# Core.net
KiCad netlist of a schematic drawn in Altium Designer
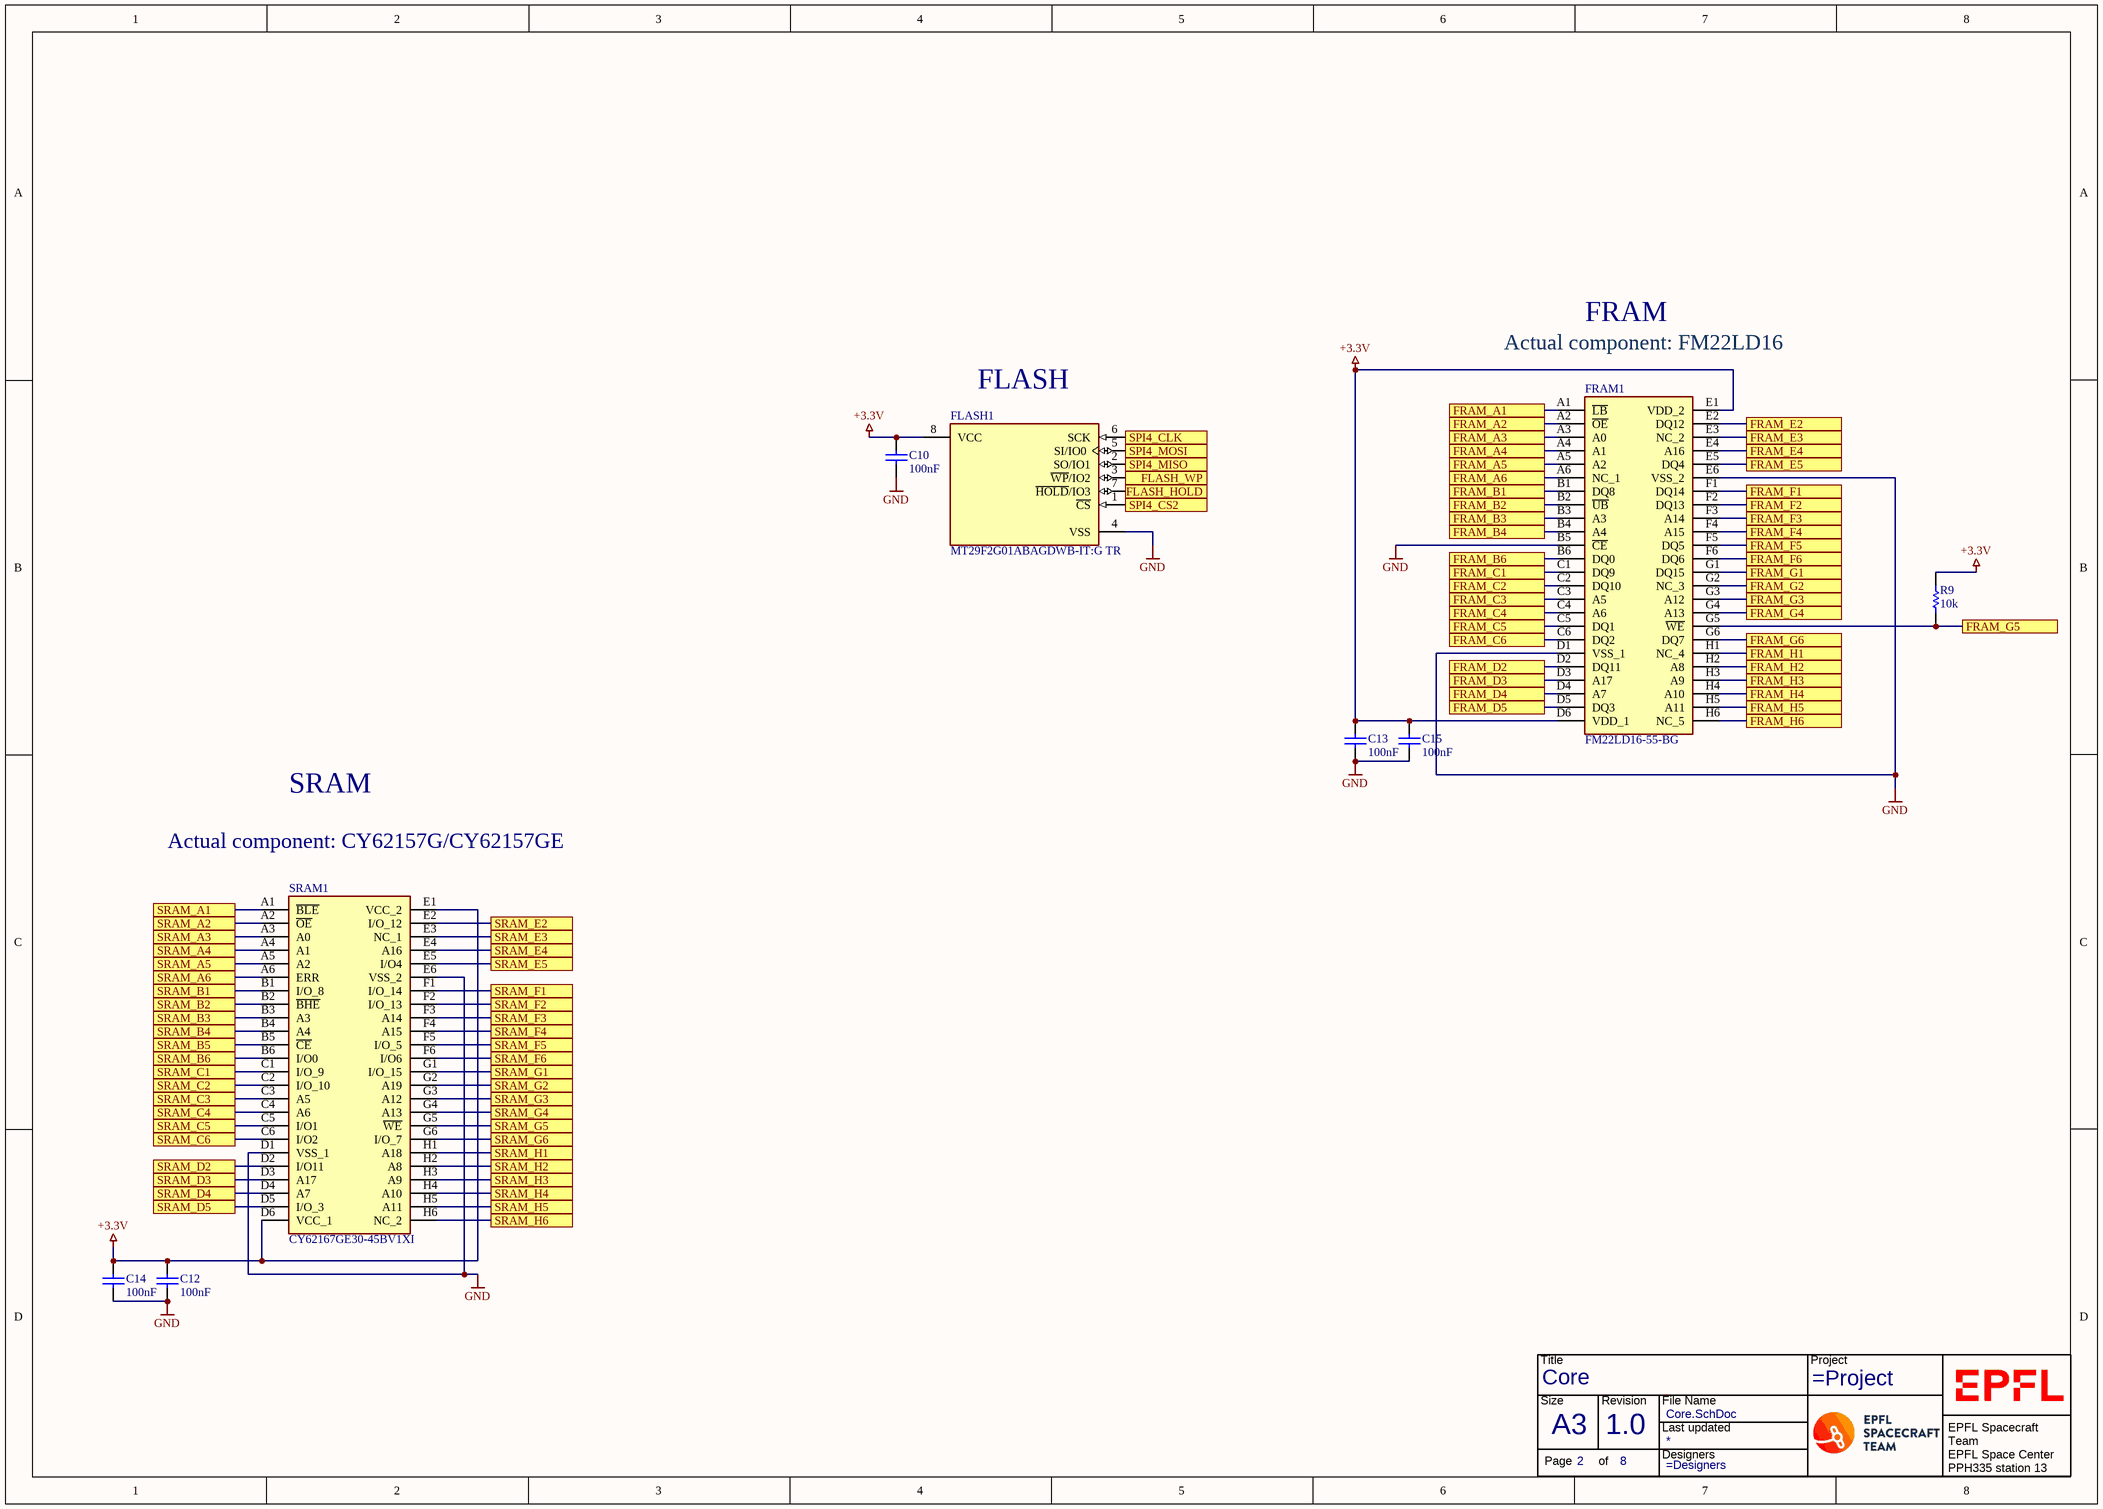
[diagram p0: Core.SchDoc]

(export (version "E")
  (design (tool "Eeschema 10.0.6"))
  (components
    (comp (ref "*")
      (value "TitleBlock")
      (description "Title Block with generall information")
      (libsource (lib "CHESSOBC_rev1") (part "TitleBlock"))
    )
    (comp (ref "C10")
      (value "100nF")
      (footprint "CAPC1005X60X30ML05T10")
      (fields (field (name "MANUFACTURER") "Kemet") (field (name "PART NUMBER") "C0402C104K8PACTU"))
      (libsource (lib "Altium Content Vault") (part "CAP"))
    )
    (comp (ref "C12")
      (value "100nF")
      (footprint "CAPC1005X60X30ML05T10")
      (fields (field (name "MANUFACTURER") "Kemet") (field (name "PART NUMBER") "C0402C104K8PACTU"))
      (libsource (lib "Altium Content Vault") (part "CAP"))
    )
    (comp (ref "C13")
      (value "100nF")
      (footprint "CAPC1005X60X30ML05T10")
      (fields (field (name "MANUFACTURER") "Kemet") (field (name "PART NUMBER") "C0402C104K8PACTU"))
      (libsource (lib "Altium Content Vault") (part "CAP"))
    )
    (comp (ref "C14")
      (value "100nF")
      (footprint "CAPC1005X60X30ML05T10")
      (fields (field (name "MANUFACTURER") "Kemet") (field (name "PART NUMBER") "C0402C104K8PACTU"))
      (libsource (lib "Altium Content Vault") (part "CAP"))
    )
    (comp (ref "C15")
      (value "100nF")
      (footprint "CAPC1005X60X30ML05T10")
      (fields (field (name "MANUFACTURER") "Kemet") (field (name "PART NUMBER") "C0402C104K8PACTU"))
      (libsource (lib "Altium Content Vault") (part "CAP"))
    )
    (comp (ref "FLASH1")
      (value "MT29F2G01ABAGDWB-IT:G TR")
      (footprint "FP-WB-IPC_C")
      (description "IC FLASH 2G SPI 8UPDFN")
      (libsource (lib "Altium Content Vault") (part "9be75b636f0445a1fe91e7781565aa2"))
    )
    (comp (ref "FRAM1")
      (value "FM22LD16-55-BG")
      (footprint "SamacSys:BGA48C75P6X8_600X800X120")
      (description "Integrated Circuit")
      (fields (field (name "MOUSER PART NUMBER") "877-FM22LD16-55-BG"))
      (libsource (lib "*") (part "FM22LD16-55-BG"))
    )
    (comp (ref "R9")
      (value "10k")
      (footprint "RESC1005X40X25LL05T10")
      (fields (field (name "PART NUMBER") "RC0402FR-0710KL") (field (name "MANUFACTURER") "Yageo / Phycomp"))
      (libsource (lib "Altium Content Vault") (part "RES"))
    )
    (comp (ref "SRAM1")
      (value "CY62167GE30-45BV1XI")
      (footprint "SamacSys:BGA48C75P6X8_600X800X100")
      (description "Integrated Circuit")
      (fields (field (name "MOUSER PART NUMBER") "727-CY62167GE30BV1XI"))
      (libsource (lib "*") (part "CY62167GE30-45BV1XI"))
    )
  )
  (nets
    (net (code "1") (name "+3.3V") (class "Default")
      (node (ref "C10") (pin "2") (pinfunction "2_2") (pintype "passive"))
      (node (ref "C12") (pin "2") (pinfunction "2_2") (pintype "passive"))
      (node (ref "C13") (pin "2") (pinfunction "2_2") (pintype "passive"))
      (node (ref "C14") (pin "2") (pinfunction "2_2") (pintype "passive"))
      (node (ref "C15") (pin "2") (pinfunction "2_2") (pintype "passive"))
      (node (ref "FLASH1") (pin "8") (pinfunction "VCC_8") (pintype "power_in"))
      (node (ref "FRAM1") (pin "D6") (pinfunction "VDD_1_D6") (pintype "passive"))
      (node (ref "FRAM1") (pin "E1") (pinfunction "VDD_2_E1") (pintype "passive"))
      (node (ref "R9") (pin "2") (pinfunction "2_2") (pintype "passive"))
      (node (ref "SRAM1") (pin "D6") (pinfunction "VCC_1_D6") (pintype "passive"))
      (node (ref "SRAM1") (pin "E1") (pinfunction "VCC_2_E1") (pintype "passive"))
    )
    (net (code "2") (name "/FLASH_HOLD") (class "Default")
      (node (ref "FLASH1") (pin "7") (pinfunction "~{HOLD}/IO3_7") (pintype "bidirectional"))
    )
    (net (code "3") (name "/FLASH_WP") (class "Default")
      (node (ref "FLASH1") (pin "3") (pinfunction "~{WP}/IO2_3") (pintype "bidirectional"))
    )
    (net (code "4") (name "/FRAM_A1") (class "Default")
      (node (ref "FRAM1") (pin "A1") (pinfunction "~{LB}_A1") (pintype "passive"))
    )
    (net (code "5") (name "/FRAM_A2") (class "Default")
      (node (ref "FRAM1") (pin "A2") (pinfunction "~{OE}_A2") (pintype "passive"))
    )
    (net (code "6") (name "/FRAM_A3") (class "Default")
      (node (ref "FRAM1") (pin "A3") (pinfunction "A0_A3") (pintype "passive"))
    )
    (net (code "7") (name "/FRAM_A4") (class "Default")
      (node (ref "FRAM1") (pin "A4") (pinfunction "A1_A4") (pintype "passive"))
    )
    (net (code "8") (name "/FRAM_A5") (class "Default")
      (node (ref "FRAM1") (pin "A5") (pinfunction "A2_A5") (pintype "passive"))
    )
    (net (code "9") (name "/FRAM_A6") (class "Default")
      (node (ref "FRAM1") (pin "A6") (pinfunction "NC_1_A6") (pintype "passive"))
    )
    (net (code "10") (name "/FRAM_B1") (class "Default")
      (node (ref "FRAM1") (pin "B1") (pinfunction "DQ8_B1") (pintype "passive"))
    )
    (net (code "11") (name "/FRAM_B2") (class "Default")
      (node (ref "FRAM1") (pin "B2") (pinfunction "~{UB}_B2") (pintype "passive"))
    )
    (net (code "12") (name "/FRAM_B3") (class "Default")
      (node (ref "FRAM1") (pin "B3") (pinfunction "A3_B3") (pintype "passive"))
    )
    (net (code "13") (name "/FRAM_B4") (class "Default")
      (node (ref "FRAM1") (pin "B4") (pinfunction "A4_B4") (pintype "passive"))
    )
    (net (code "14") (name "/FRAM_B6") (class "Default")
      (node (ref "FRAM1") (pin "B6") (pinfunction "DQ0_B6") (pintype "passive"))
    )
    (net (code "15") (name "/FRAM_C1") (class "Default")
      (node (ref "FRAM1") (pin "C1") (pinfunction "DQ9_C1") (pintype "passive"))
    )
    (net (code "16") (name "/FRAM_C2") (class "Default")
      (node (ref "FRAM1") (pin "C2") (pinfunction "DQ10_C2") (pintype "passive"))
    )
    (net (code "17") (name "/FRAM_C3") (class "Default")
      (node (ref "FRAM1") (pin "C3") (pinfunction "A5_C3") (pintype "passive"))
    )
    (net (code "18") (name "/FRAM_C4") (class "Default")
      (node (ref "FRAM1") (pin "C4") (pinfunction "A6_C4") (pintype "passive"))
    )
    (net (code "19") (name "/FRAM_C5") (class "Default")
      (node (ref "FRAM1") (pin "C5") (pinfunction "DQ1_C5") (pintype "passive"))
    )
    (net (code "20") (name "/FRAM_C6") (class "Default")
      (node (ref "FRAM1") (pin "C6") (pinfunction "DQ2_C6") (pintype "passive"))
    )
    (net (code "21") (name "/FRAM_D2") (class "Default")
      (node (ref "FRAM1") (pin "D2") (pinfunction "DQ11_D2") (pintype "passive"))
    )
    (net (code "22") (name "/FRAM_D3") (class "Default")
      (node (ref "FRAM1") (pin "D3") (pinfunction "A17_D3") (pintype "passive"))
    )
    (net (code "23") (name "/FRAM_D4") (class "Default")
      (node (ref "FRAM1") (pin "D4") (pinfunction "A7_D4") (pintype "passive"))
    )
    (net (code "24") (name "/FRAM_D5") (class "Default")
      (node (ref "FRAM1") (pin "D5") (pinfunction "DQ3_D5") (pintype "passive"))
    )
    (net (code "25") (name "/FRAM_E2") (class "Default")
      (node (ref "FRAM1") (pin "E2") (pinfunction "DQ12_E2") (pintype "passive"))
    )
    (net (code "26") (name "/FRAM_E3") (class "Default")
      (node (ref "FRAM1") (pin "E3") (pinfunction "NC_2_E3") (pintype "passive"))
    )
    (net (code "27") (name "/FRAM_E4") (class "Default")
      (node (ref "FRAM1") (pin "E4") (pinfunction "A16_E4") (pintype "passive"))
    )
    (net (code "28") (name "/FRAM_E5") (class "Default")
      (node (ref "FRAM1") (pin "E5") (pinfunction "DQ4_E5") (pintype "passive"))
    )
    (net (code "29") (name "/FRAM_F1") (class "Default")
      (node (ref "FRAM1") (pin "F1") (pinfunction "DQ14_F1") (pintype "passive"))
    )
    (net (code "30") (name "/FRAM_F2") (class "Default")
      (node (ref "FRAM1") (pin "F2") (pinfunction "DQ13_F2") (pintype "passive"))
    )
    (net (code "31") (name "/FRAM_F3") (class "Default")
      (node (ref "FRAM1") (pin "F3") (pinfunction "A14_F3") (pintype "passive"))
    )
    (net (code "32") (name "/FRAM_F4") (class "Default")
      (node (ref "FRAM1") (pin "F4") (pinfunction "A15_F4") (pintype "passive"))
    )
    (net (code "33") (name "/FRAM_F5") (class "Default")
      (node (ref "FRAM1") (pin "F5") (pinfunction "DQ5_F5") (pintype "passive"))
    )
    (net (code "34") (name "/FRAM_F6") (class "Default")
      (node (ref "FRAM1") (pin "F6") (pinfunction "DQ6_F6") (pintype "passive"))
    )
    (net (code "35") (name "/FRAM_G1") (class "Default")
      (node (ref "FRAM1") (pin "G1") (pinfunction "DQ15_G1") (pintype "passive"))
    )
    (net (code "36") (name "/FRAM_G2") (class "Default")
      (node (ref "FRAM1") (pin "G2") (pinfunction "NC_3_G2") (pintype "passive"))
    )
    (net (code "37") (name "/FRAM_G3") (class "Default")
      (node (ref "FRAM1") (pin "G3") (pinfunction "A12_G3") (pintype "passive"))
    )
    (net (code "38") (name "/FRAM_G4") (class "Default")
      (node (ref "FRAM1") (pin "G4") (pinfunction "A13_G4") (pintype "passive"))
    )
    (net (code "39") (name "/FRAM_G5") (class "Default")
      (node (ref "FRAM1") (pin "G5") (pinfunction "~{WE}_G5") (pintype "passive"))
      (node (ref "R9") (pin "1") (pinfunction "1_1") (pintype "passive"))
    )
    (net (code "40") (name "/FRAM_G6") (class "Default")
      (node (ref "FRAM1") (pin "G6") (pinfunction "DQ7_G6") (pintype "passive"))
    )
    (net (code "41") (name "/FRAM_H1") (class "Default")
      (node (ref "FRAM1") (pin "H1") (pinfunction "NC_4_H1") (pintype "passive"))
    )
    (net (code "42") (name "/FRAM_H2") (class "Default")
      (node (ref "FRAM1") (pin "H2") (pinfunction "A8_H2") (pintype "passive"))
    )
    (net (code "43") (name "/FRAM_H3") (class "Default")
      (node (ref "FRAM1") (pin "H3") (pinfunction "A9_H3") (pintype "passive"))
    )
    (net (code "44") (name "/FRAM_H4") (class "Default")
      (node (ref "FRAM1") (pin "H4") (pinfunction "A10_H4") (pintype "passive"))
    )
    (net (code "45") (name "/FRAM_H5") (class "Default")
      (node (ref "FRAM1") (pin "H5") (pinfunction "A11_H5") (pintype "passive"))
    )
    (net (code "46") (name "/FRAM_H6") (class "Default")
      (node (ref "FRAM1") (pin "H6") (pinfunction "NC_5_H6") (pintype "passive"))
    )
    (net (code "47") (name "/SPI4_CLK") (class "Default")
      (node (ref "FLASH1") (pin "6") (pinfunction "SCK_6") (pintype "input"))
    )
    (net (code "48") (name "/SPI4_CS2") (class "Default")
      (node (ref "FLASH1") (pin "1") (pinfunction "~{CS}_1") (pintype "input"))
    )
    (net (code "49") (name "/SPI4_MISO") (class "Default")
      (node (ref "FLASH1") (pin "2") (pinfunction "SO/IO1_2") (pintype "bidirectional"))
    )
    (net (code "50") (name "/SPI4_MOSI") (class "Default")
      (node (ref "FLASH1") (pin "5") (pinfunction "SI/IO0_5") (pintype "bidirectional"))
    )
    (net (code "51") (name "/SRAM_A1") (class "Default")
      (node (ref "SRAM1") (pin "A1") (pinfunction "~{BLE}_A1") (pintype "passive"))
    )
    (net (code "52") (name "/SRAM_A2") (class "Default")
      (node (ref "SRAM1") (pin "A2") (pinfunction "~{OE}_A2") (pintype "passive"))
    )
    (net (code "53") (name "/SRAM_A3") (class "Default")
      (node (ref "SRAM1") (pin "A3") (pinfunction "A0_A3") (pintype "passive"))
    )
    (net (code "54") (name "/SRAM_A4") (class "Default")
      (node (ref "SRAM1") (pin "A4") (pinfunction "A1_A4") (pintype "passive"))
    )
    (net (code "55") (name "/SRAM_A5") (class "Default")
      (node (ref "SRAM1") (pin "A5") (pinfunction "A2_A5") (pintype "passive"))
    )
    (net (code "56") (name "/SRAM_A6") (class "Default")
      (node (ref "SRAM1") (pin "A6") (pinfunction "ERR_A6") (pintype "passive"))
    )
    (net (code "57") (name "/SRAM_B1") (class "Default")
      (node (ref "SRAM1") (pin "B1") (pinfunction "I/O_8_B1") (pintype "passive"))
    )
    (net (code "58") (name "/SRAM_B2") (class "Default")
      (node (ref "SRAM1") (pin "B2") (pinfunction "~{BHE}_B2") (pintype "passive"))
    )
    (net (code "59") (name "/SRAM_B3") (class "Default")
      (node (ref "SRAM1") (pin "B3") (pinfunction "A3_B3") (pintype "passive"))
    )
    (net (code "60") (name "/SRAM_B4") (class "Default")
      (node (ref "SRAM1") (pin "B4") (pinfunction "A4_B4") (pintype "passive"))
    )
    (net (code "61") (name "/SRAM_B5") (class "Default")
      (node (ref "SRAM1") (pin "B5") (pinfunction "~{CE}_B5") (pintype "passive"))
    )
    (net (code "62") (name "/SRAM_B6") (class "Default")
      (node (ref "SRAM1") (pin "B6") (pinfunction "I/O0_B6") (pintype "passive"))
    )
    (net (code "63") (name "/SRAM_C1") (class "Default")
      (node (ref "SRAM1") (pin "C1") (pinfunction "I/O_9_C1") (pintype "passive"))
    )
    (net (code "64") (name "/SRAM_C2") (class "Default")
      (node (ref "SRAM1") (pin "C2") (pinfunction "I/O_10_C2") (pintype "passive"))
    )
    (net (code "65") (name "/SRAM_C3") (class "Default")
      (node (ref "SRAM1") (pin "C3") (pinfunction "A5_C3") (pintype "passive"))
    )
    (net (code "66") (name "/SRAM_C4") (class "Default")
      (node (ref "SRAM1") (pin "C4") (pinfunction "A6_C4") (pintype "passive"))
    )
    (net (code "67") (name "/SRAM_C5") (class "Default")
      (node (ref "SRAM1") (pin "C5") (pinfunction "I/O1_C5") (pintype "passive"))
    )
    (net (code "68") (name "/SRAM_C6") (class "Default")
      (node (ref "SRAM1") (pin "C6") (pinfunction "I/O2_C6") (pintype "passive"))
    )
    (net (code "69") (name "/SRAM_D2") (class "Default")
      (node (ref "SRAM1") (pin "D2") (pinfunction "I/O11_D2") (pintype "passive"))
    )
    (net (code "70") (name "/SRAM_D3") (class "Default")
      (node (ref "SRAM1") (pin "D3") (pinfunction "A17_D3") (pintype "passive"))
    )
    (net (code "71") (name "/SRAM_D4") (class "Default")
      (node (ref "SRAM1") (pin "D4") (pinfunction "A7_D4") (pintype "passive"))
    )
    (net (code "72") (name "/SRAM_D5") (class "Default")
      (node (ref "SRAM1") (pin "D5") (pinfunction "I/O_3_D5") (pintype "passive"))
    )
    (net (code "73") (name "/SRAM_E2") (class "Default")
      (node (ref "SRAM1") (pin "E2") (pinfunction "I/O_12_E2") (pintype "passive"))
    )
    (net (code "74") (name "/SRAM_E3") (class "Default")
      (node (ref "SRAM1") (pin "E3") (pinfunction "NC_1_E3") (pintype "passive"))
    )
    (net (code "75") (name "/SRAM_E4") (class "Default")
      (node (ref "SRAM1") (pin "E4") (pinfunction "A16_E4") (pintype "passive"))
    )
    (net (code "76") (name "/SRAM_E5") (class "Default")
      (node (ref "SRAM1") (pin "E5") (pinfunction "I/O4_E5") (pintype "passive"))
    )
    (net (code "77") (name "/SRAM_F1") (class "Default")
      (node (ref "SRAM1") (pin "F1") (pinfunction "I/O_14_F1") (pintype "passive"))
    )
    (net (code "78") (name "/SRAM_F2") (class "Default")
      (node (ref "SRAM1") (pin "F2") (pinfunction "I/O_13_F2") (pintype "passive"))
    )
    (net (code "79") (name "/SRAM_F3") (class "Default")
      (node (ref "SRAM1") (pin "F3") (pinfunction "A14_F3") (pintype "passive"))
    )
    (net (code "80") (name "/SRAM_F4") (class "Default")
      (node (ref "SRAM1") (pin "F4") (pinfunction "A15_F4") (pintype "passive"))
    )
    (net (code "81") (name "/SRAM_F5") (class "Default")
      (node (ref "SRAM1") (pin "F5") (pinfunction "I/O_5_F5") (pintype "passive"))
    )
    (net (code "82") (name "/SRAM_F6") (class "Default")
      (node (ref "SRAM1") (pin "F6") (pinfunction "I/O6_F6") (pintype "passive"))
    )
    (net (code "83") (name "/SRAM_G1") (class "Default")
      (node (ref "SRAM1") (pin "G1") (pinfunction "I/O_15_G1") (pintype "passive"))
    )
    (net (code "84") (name "/SRAM_G2") (class "Default")
      (node (ref "SRAM1") (pin "G2") (pinfunction "A19_G2") (pintype "passive"))
    )
    (net (code "85") (name "/SRAM_G3") (class "Default")
      (node (ref "SRAM1") (pin "G3") (pinfunction "A12_G3") (pintype "passive"))
    )
    (net (code "86") (name "/SRAM_G4") (class "Default")
      (node (ref "SRAM1") (pin "G4") (pinfunction "A13_G4") (pintype "passive"))
    )
    (net (code "87") (name "/SRAM_G5") (class "Default")
      (node (ref "SRAM1") (pin "G5") (pinfunction "~{WE}_G5") (pintype "passive"))
    )
    (net (code "88") (name "/SRAM_G6") (class "Default")
      (node (ref "SRAM1") (pin "G6") (pinfunction "I/O_7_G6") (pintype "passive"))
    )
    (net (code "89") (name "/SRAM_H1") (class "Default")
      (node (ref "SRAM1") (pin "H1") (pinfunction "A18_H1") (pintype "passive"))
    )
    (net (code "90") (name "/SRAM_H2") (class "Default")
      (node (ref "SRAM1") (pin "H2") (pinfunction "A8_H2") (pintype "passive"))
    )
    (net (code "91") (name "/SRAM_H3") (class "Default")
      (node (ref "SRAM1") (pin "H3") (pinfunction "A9_H3") (pintype "passive"))
    )
    (net (code "92") (name "/SRAM_H4") (class "Default")
      (node (ref "SRAM1") (pin "H4") (pinfunction "A10_H4") (pintype "passive"))
    )
    (net (code "93") (name "/SRAM_H5") (class "Default")
      (node (ref "SRAM1") (pin "H5") (pinfunction "A11_H5") (pintype "passive"))
    )
    (net (code "94") (name "/SRAM_H6") (class "Default")
      (node (ref "SRAM1") (pin "H6") (pinfunction "NC_2_H6") (pintype "passive"))
    )
    (net (code "95") (name "GND") (class "Default")
      (node (ref "C10") (pin "1") (pinfunction "1_1") (pintype "passive"))
      (node (ref "C12") (pin "1") (pinfunction "1_1") (pintype "passive"))
      (node (ref "C13") (pin "1") (pinfunction "1_1") (pintype "passive"))
      (node (ref "C14") (pin "1") (pinfunction "1_1") (pintype "passive"))
      (node (ref "C15") (pin "1") (pinfunction "1_1") (pintype "passive"))
      (node (ref "FLASH1") (pin "4") (pinfunction "VSS_4") (pintype "power_in"))
      (node (ref "FRAM1") (pin "B5") (pinfunction "~{CE}_B5") (pintype "passive"))
      (node (ref "FRAM1") (pin "D1") (pinfunction "VSS_1_D1") (pintype "passive"))
      (node (ref "FRAM1") (pin "E6") (pinfunction "VSS_2_E6") (pintype "passive"))
      (node (ref "SRAM1") (pin "D1") (pinfunction "VSS_1_D1") (pintype "passive"))
      (node (ref "SRAM1") (pin "E6") (pinfunction "VSS_2_E6") (pintype "passive"))
    )
  )
)
